# working.net
KiCad netlist of a schematic drawn in EAGLE
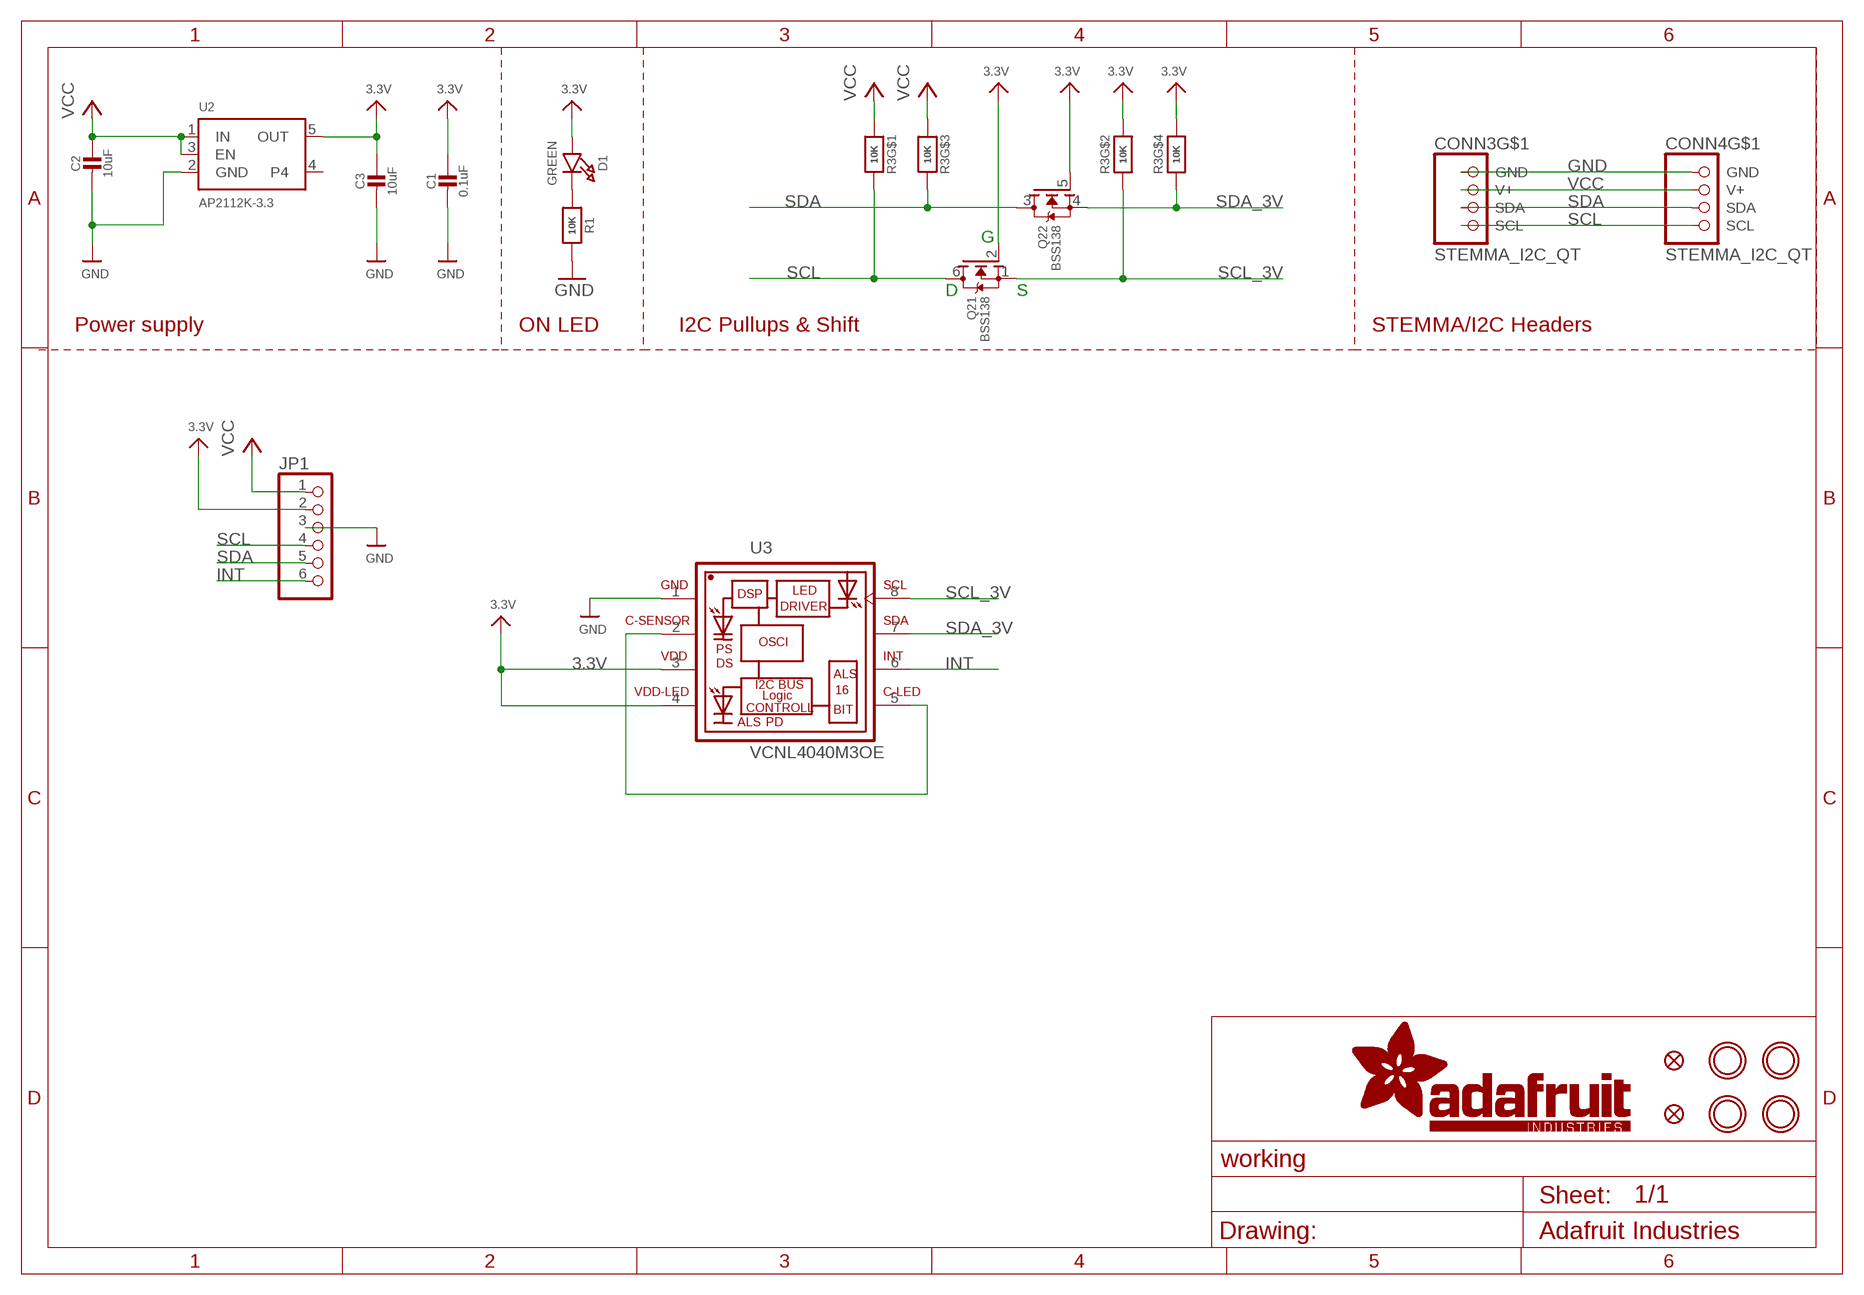
[diagram p0: schematic, sheet 1]

(export (version "E")
  (design (tool "Eeschema 10.0.6"))
  (components
    (comp (ref "C1")
      (value "0.1uF")
      (footprint "eagle-import:0603-NO")
      (libsource (lib "eagle-import") (part "CAP_CERAMIC0603_NO"))
    )
    (comp (ref "C2")
      (value "10uF")
      (footprint "eagle-import:0805-NO")
      (libsource (lib "eagle-import") (part "CAP_CERAMIC0805-NOOUTLINE"))
    )
    (comp (ref "C3")
      (value "10uF")
      (footprint "eagle-import:0805-NO")
      (libsource (lib "eagle-import") (part "CAP_CERAMIC0805-NOOUTLINE"))
    )
    (comp (ref "CONN3")
      (value "STEMMA_I2C_QT")
      (footprint "eagle-import:JST_SH4")
      (libsource (lib "eagle-import") (part "STEMMA_I2C_QT"))
    )
    (comp (ref "CONN4")
      (value "STEMMA_I2C_QT")
      (footprint "eagle-import:JST_SH4")
      (libsource (lib "eagle-import") (part "STEMMA_I2C_QT"))
    )
    (comp (ref "D1")
      (value "GREEN")
      (footprint "eagle-import:CHIPLED_0603_NOOUTLINE")
      (libsource (lib "eagle-import") (part "LED0603_NOOUTLINE"))
    )
    (comp (ref "FID3")
      (value "FIDUCIAL_1MM")
      (footprint "eagle-import:FIDUCIAL_1MM")
      (libsource (lib "eagle-import") (part "FIDUCIAL_1MM"))
    )
    (comp (ref "FID4")
      (value "FIDUCIAL_1MM")
      (footprint "eagle-import:FIDUCIAL_1MM")
      (libsource (lib "eagle-import") (part "FIDUCIAL_1MM"))
    )
    (comp (ref "JP1")
      (value "HEADER-1X670MIL")
      (footprint "eagle-import:1X06_ROUND_70")
      (libsource (lib "eagle-import") (part "HEADER-1X670MIL"))
    )
    (comp (ref "Q2")
      (value "BSS138")
      (footprint "eagle-import:SOT363")
      (libsource (lib "eagle-import") (part "MOSFET-N_DUAL"))
    )
    (comp (ref "R1")
      (value "10K")
      (footprint "eagle-import:0603-NO")
      (libsource (lib "eagle-import") (part "RESISTOR_0603_NOOUT"))
    )
    (comp (ref "R3")
      (value "10K")
      (footprint "eagle-import:RESPACK_4X0603")
      (libsource (lib "eagle-import") (part "RESISTOR_4PACK"))
    )
    (comp (ref "U$1")
      (value "MOUNTINGHOLE2.5")
      (footprint "eagle-import:MOUNTINGHOLE_2.5_PLATED")
      (libsource (lib "eagle-import") (part "MOUNTINGHOLE2.5"))
    )
    (comp (ref "U$17")
      (value "MOUNTINGHOLE2.5")
      (footprint "eagle-import:MOUNTINGHOLE_2.5_PLATED")
      (libsource (lib "eagle-import") (part "MOUNTINGHOLE2.5"))
    )
    (comp (ref "U$19")
      (value "MOUNTINGHOLE2.5")
      (footprint "eagle-import:MOUNTINGHOLE_2.5_PLATED")
      (libsource (lib "eagle-import") (part "MOUNTINGHOLE2.5"))
    )
    (comp (ref "U$21")
      (value "MOUNTINGHOLE2.5")
      (footprint "eagle-import:MOUNTINGHOLE_2.5_PLATED")
      (libsource (lib "eagle-import") (part "MOUNTINGHOLE2.5"))
    )
    (comp (ref "U2")
      (value "AP2112K-3.3")
      (footprint "eagle-import:SOT23-5")
      (libsource (lib "eagle-import") (part "VREG_SOT23-5"))
    )
    (comp (ref "U3")
      (value "VCNL4040M3OE")
      (footprint "eagle-import:VISHAY_VCNL4040_4X2X1.1")
      (fields (field (name "MF") "Vishay"))
      (libsource (lib "eagle-import") (part "VCNL4040M3OE"))
    )
  )
  (nets
    (net (code "1") (name "/INT") (class "Default")
      (node (ref "JP1") (pin "6") (pinfunction "6_6") (pintype "passive"))
      (node (ref "U3") (pin "6") (pinfunction "INT_6") (pintype "output"))
    )
    (net (code "2") (name "/SCL") (class "Default")
      (node (ref "CONN3") (pin "4") (pinfunction "SCL_4") (pintype "passive"))
      (node (ref "CONN4") (pin "4") (pinfunction "SCL_4") (pintype "passive"))
      (node (ref "JP1") (pin "4") (pinfunction "4_4") (pintype "passive"))
      (node (ref "Q2") (pin "6") (pinfunction "D_6") (pintype "bidirectional"))
      (node (ref "R3") (pin "8") (pinfunction "2_8") (pintype "passive"))
    )
    (net (code "3") (name "/SCL_3V") (class "Default")
      (node (ref "Q2") (pin "1") (pinfunction "S_1") (pintype "bidirectional"))
      (node (ref "R3") (pin "7") (pinfunction "2_7") (pintype "passive"))
      (node (ref "U3") (pin "8") (pinfunction "SCL_8") (pintype "input"))
    )
    (net (code "4") (name "/SDA") (class "Default")
      (node (ref "CONN3") (pin "3") (pinfunction "SDA_3") (pintype "passive"))
      (node (ref "CONN4") (pin "3") (pinfunction "SDA_3") (pintype "passive"))
      (node (ref "JP1") (pin "5") (pinfunction "5_5") (pintype "passive"))
      (node (ref "Q2") (pin "3") (pinfunction "D_3") (pintype "bidirectional"))
      (node (ref "R3") (pin "6") (pinfunction "2_6") (pintype "passive"))
    )
    (net (code "5") (name "/SDA_3V") (class "Default")
      (node (ref "Q2") (pin "4") (pinfunction "S_4") (pintype "bidirectional"))
      (node (ref "R3") (pin "5") (pinfunction "2_5") (pintype "passive"))
      (node (ref "U3") (pin "7") (pinfunction "SDA_7") (pintype "bidirectional"))
    )
    (net (code "6") (name "3.3V") (class "Default")
      (node (ref "C1") (pin "1") (pinfunction "1_1") (pintype "passive"))
      (node (ref "C3") (pin "1") (pinfunction "1_1") (pintype "passive"))
      (node (ref "D1") (pin "A") (pinfunction "A_A") (pintype "passive"))
      (node (ref "JP1") (pin "2") (pinfunction "2_2") (pintype "passive"))
      (node (ref "Q2") (pin "2") (pinfunction "G_2") (pintype "bidirectional"))
      (node (ref "Q2") (pin "5") (pinfunction "G_5") (pintype "bidirectional"))
      (node (ref "R3") (pin "2") (pinfunction "1_2") (pintype "passive"))
      (node (ref "R3") (pin "4") (pinfunction "1_4") (pintype "passive"))
      (node (ref "U2") (pin "5") (pinfunction "OUT_5") (pintype "power_in"))
      (node (ref "U3") (pin "3") (pinfunction "VDD_3") (pintype "power_in"))
      (node (ref "U3") (pin "4") (pinfunction "VDD-LED_4") (pintype "power_in"))
    )
    (net (code "7") (name "GND") (class "Default")
      (node (ref "C1") (pin "2") (pinfunction "2_2") (pintype "passive"))
      (node (ref "C2") (pin "2") (pinfunction "2_2") (pintype "passive"))
      (node (ref "C3") (pin "2") (pinfunction "2_2") (pintype "passive"))
      (node (ref "CONN3") (pin "1") (pinfunction "GND_1") (pintype "passive"))
      (node (ref "CONN4") (pin "1") (pinfunction "GND_1") (pintype "passive"))
      (node (ref "JP1") (pin "3") (pinfunction "3_3") (pintype "passive"))
      (node (ref "R1") (pin "2") (pinfunction "2_2") (pintype "passive"))
      (node (ref "U2") (pin "2") (pinfunction "GND_2") (pintype "power_in"))
      (node (ref "U3") (pin "1") (pinfunction "GND_1") (pintype "power_in"))
    )
    (net (code "8") (name "Net-(D1-PadC)") (class "Default")
      (node (ref "D1") (pin "C") (pinfunction "C_C") (pintype "passive"))
      (node (ref "R1") (pin "1") (pinfunction "1_1") (pintype "passive"))
    )
    (net (code "9") (name "Net-(U3-C-LED)") (class "Default")
      (node (ref "U3") (pin "2") (pinfunction "C-SENSOR_2") (pintype "output"))
      (node (ref "U3") (pin "5") (pinfunction "C-LED_5") (pintype "output"))
    )
    (net (code "10") (name "VCC") (class "Default")
      (node (ref "C2") (pin "1") (pinfunction "1_1") (pintype "passive"))
      (node (ref "CONN3") (pin "2") (pinfunction "V+_2") (pintype "passive"))
      (node (ref "CONN4") (pin "2") (pinfunction "V+_2") (pintype "passive"))
      (node (ref "JP1") (pin "1") (pinfunction "1_1") (pintype "passive"))
      (node (ref "R3") (pin "1") (pinfunction "1_1") (pintype "passive"))
      (node (ref "R3") (pin "3") (pinfunction "1_3") (pintype "passive"))
      (node (ref "U2") (pin "1") (pinfunction "IN_1") (pintype "power_in"))
      (node (ref "U2") (pin "3") (pinfunction "EN_3") (pintype "input"))
    )
    (net (code "11") (name "unconnected-(U2-P4-Pad4)") (class "Default")
      (node (ref "U2") (pin "4") (pinfunction "P4_4") (pintype "bidirectional"))
    )
  )
)
